# COVER_PAGE.net
KiCad netlist of a schematic drawn in Altium Designer
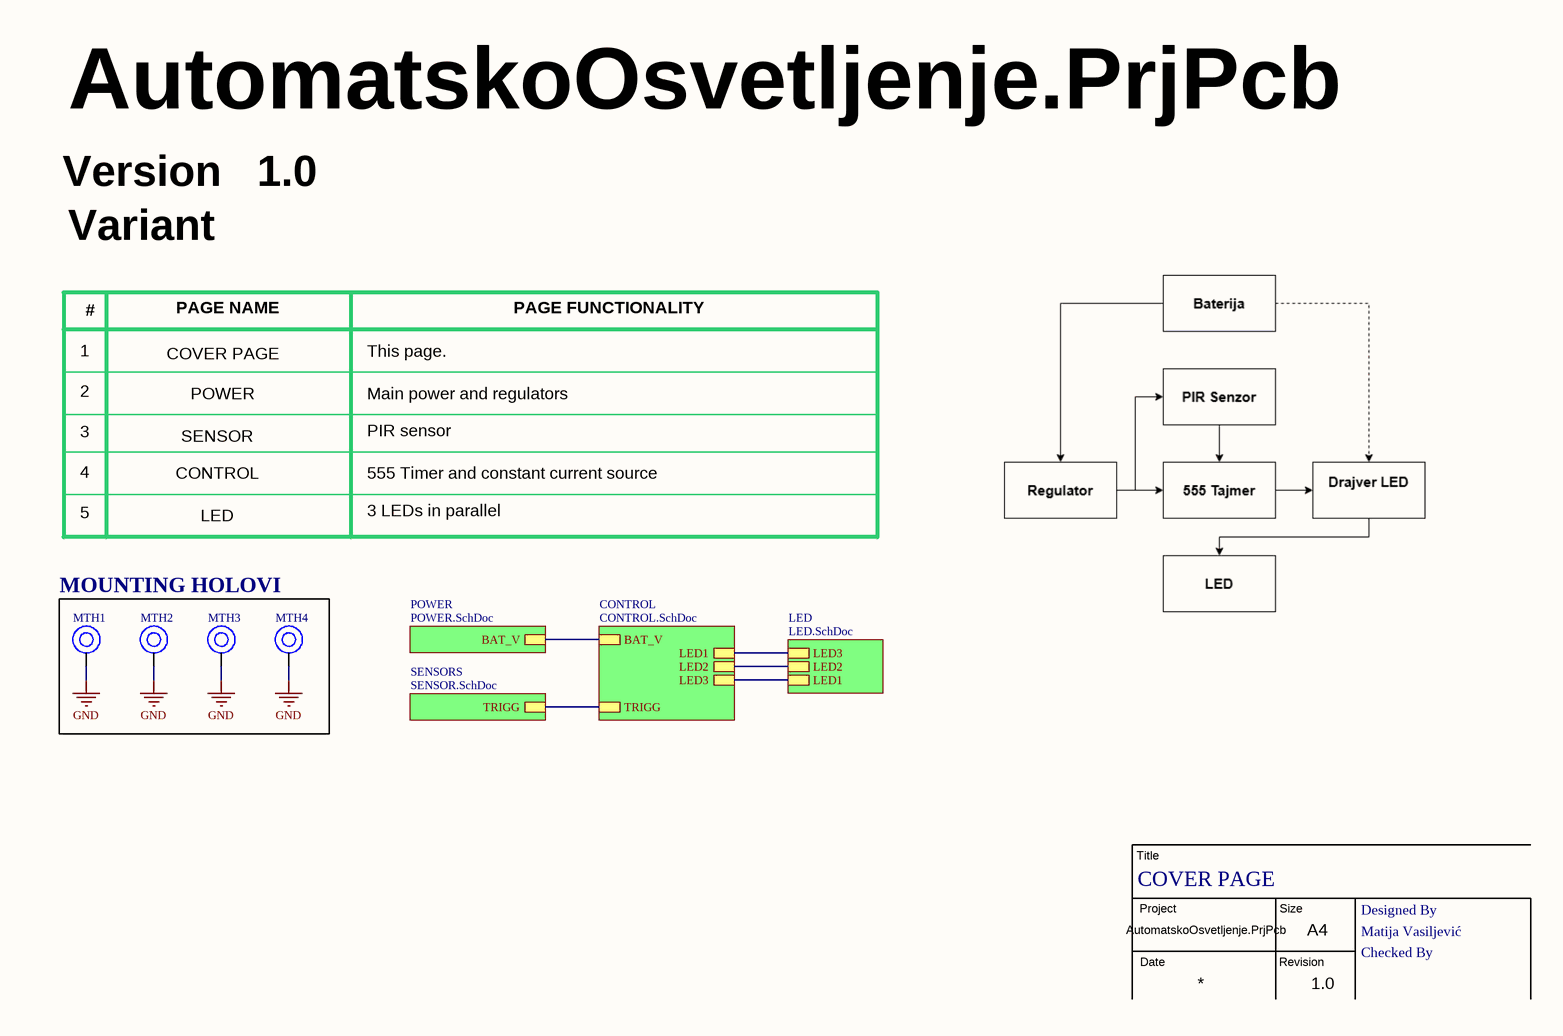
[diagram p0: COVER PAGE.SchDoc]

(export (version "E")
  (design (tool "Eeschema 10.0.6"))
  (components
    (comp (ref "MTH1")
      (value "MTH")
      (footprint "MOUNTING_HOLE_M3")
      (description "Mounting hole")
      (libsource (lib "Library-AutomatskoOsvetljenje") (part "MTH"))
    )
    (comp (ref "MTH2")
      (value "MTH")
      (footprint "MOUNTING_HOLE_M3")
      (description "Mounting hole")
      (libsource (lib "Library-AutomatskoOsvetljenje") (part "MTH"))
    )
    (comp (ref "MTH3")
      (value "MTH")
      (footprint "MOUNTING_HOLE_M3")
      (description "Mounting hole")
      (libsource (lib "Library-AutomatskoOsvetljenje") (part "MTH"))
    )
    (comp (ref "MTH4")
      (value "MTH")
      (footprint "MOUNTING_HOLE_M3")
      (description "Mounting hole")
      (libsource (lib "Library-AutomatskoOsvetljenje") (part "MTH"))
    )
  )
  (nets
    (net (code "6") (name "GND") (class "Default")
      (node (ref "MTH1") (pin "1") (pinfunction "1_1") (pintype "passive"))
      (node (ref "MTH2") (pin "1") (pinfunction "1_1") (pintype "passive"))
      (node (ref "MTH3") (pin "1") (pinfunction "1_1") (pintype "passive"))
      (node (ref "MTH4") (pin "1") (pinfunction "1_1") (pintype "passive"))
    )
  )
)
